# 4_Shutdown.net
KiCad netlist of a schematic drawn in Altium Designer
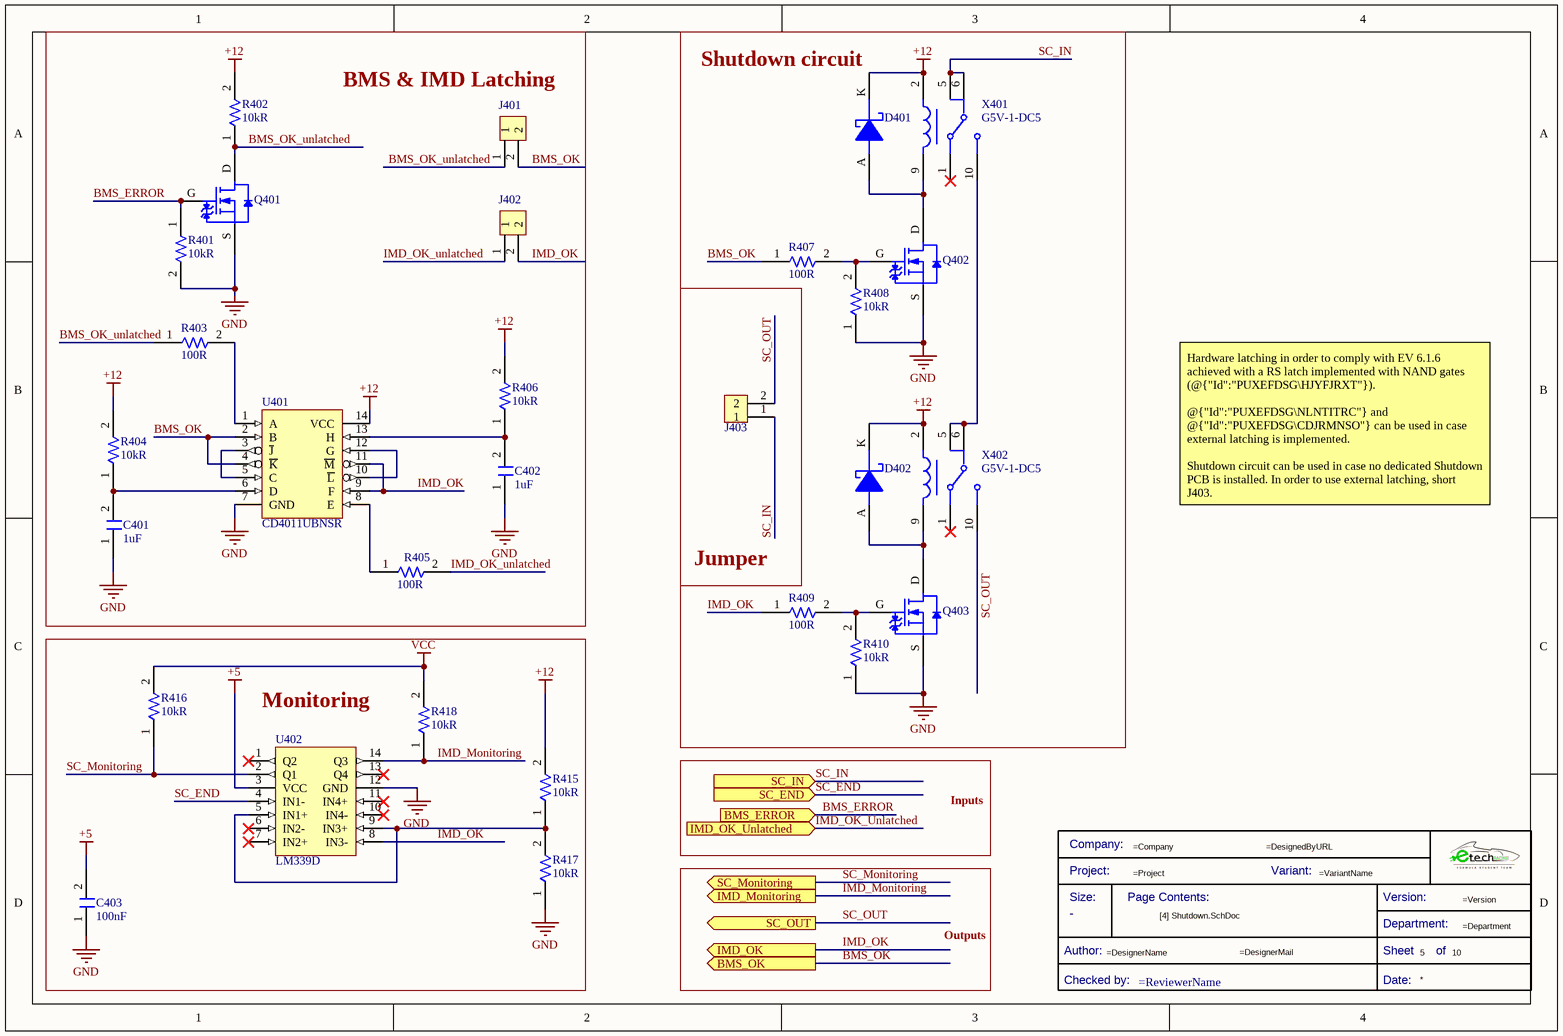
[diagram p0: [4] Shutdown.SchDoc]

(export (version "E")
  (design (tool "Eeschema 10.0.6"))
  (components
    (comp (ref "*")
      (value "Title Block_template")
      (description "Standard Title Block")
      (fields (field (name "SIZE") "-"))
      (libsource (lib "e-Tech_Racing") (part "Title Block_template"))
    )
    (comp (ref "C401")
      (value "885012207103")
      (footprint "C0805FNPC-R")
      (fields
        (field (name "TOLERANCE") "10%")
        (field (name "CAPACITANCE") "1uF")
        (field (name ".CREATOR") "GP")
      )
      (libsource (lib "Passives") (part "C1u-50V-0805FNPC-X7R"))
    )
    (comp (ref "C402")
      (value "885012207103")
      (footprint "C0805FNPC-R")
      (fields
        (field (name "TOLERANCE") "10%")
        (field (name "CAPACITANCE") "1uF")
        (field (name ".CREATOR") "GP")
      )
      (libsource (lib "Passives") (part "C1u-50V-0805FNPC-X7R"))
    )
    (comp (ref "C403")
      (value "885012207098")
      (footprint "C0805FNPC-R")
      (description "Cap, 0.1ΜF, 50V, 10%, X7R, 0805")
      (fields
        (field (name "TOLERANCE") "10%")
        (field (name "CAPACITANCE") "100nF")
        (field (name ".CREATOR") "DR")
      )
      (libsource (lib "Passives") (part "C100n-50V-0805FNPC-X7R"))
    )
    (comp (ref "D401")
      (value "MBR0530")
      (footprint "DSC-SOD123")
      (description "VR=30V IF=500mA 30pF P=410mW")
      (fields (field (name ".CREATOR") "GP"))
      (libsource (lib "Filter components") (part "DSC-0.5/30-SOD123"))
    )
    (comp (ref "D402")
      (value "MBR0530")
      (footprint "DSC-SOD123")
      (description "VR=30V IF=500mA 30pF P=410mW")
      (fields (field (name ".CREATOR") "GP"))
      (libsource (lib "Filter components") (part "DSC-0.5/30-SOD123"))
    )
    (comp (ref "J401")
      (value "61300211121")
      (footprint "J_Pinheader_1x2")
      (description "CONN HEADER 2 POS 2.54")
      (fields (field (name "MANUFACTURER") "Molex") (field (name ".CREATOR") "GP"))
      (libsource (lib "Electromechanical") (part "J_Jumper"))
    )
    (comp (ref "J402")
      (value "61300211121")
      (footprint "J_Pinheader_1x2")
      (description "CONN HEADER 2 POS 2.54")
      (fields (field (name "MANUFACTURER") "Molex") (field (name ".CREATOR") "GP"))
      (libsource (lib "Electromechanical") (part "J_Jumper"))
    )
    (comp (ref "J403")
      (value "61300211121")
      (footprint "J_Pinheader_1x2")
      (description "CONN HEADER 2 POS 2.54")
      (fields (field (name "MANUFACTURER") "Molex") (field (name ".CREATOR") "GP"))
      (libsource (lib "") (part "J_Jumper_1"))
    )
    (comp (ref "Q401")
      (value "CPH3455-TL-H")
      (footprint "TRT-NCH-3/35-CPH")
      (description "CPH3455-TL-H N-channel MOSFET Transistor; 3 A; 35 V; 3-Pin CPH")
      (fields (field (name "MANUFACTURER") "ON Semiconductor") (field (name ".CREATOR") "GP"))
      (libsource (lib "Semiconductor") (part "TRT-NCH-3/35-CPH"))
    )
    (comp (ref "Q402")
      (value "CPH3455-TL-H")
      (footprint "TRT-NCH-3/35-CPH")
      (description "CPH3455-TL-H N-channel MOSFET Transistor; 3 A; 35 V; 3-Pin CPH")
      (fields (field (name "MANUFACTURER") "ON Semiconductor") (field (name ".CREATOR") "GP"))
      (libsource (lib "Semiconductor") (part "TRT-NCH-3/35-CPH"))
    )
    (comp (ref "Q403")
      (value "CPH3455-TL-H")
      (footprint "TRT-NCH-3/35-CPH")
      (description "CPH3455-TL-H N-channel MOSFET Transistor; 3 A; 35 V; 3-Pin CPH")
      (fields (field (name "MANUFACTURER") "ON Semiconductor") (field (name ".CREATOR") "GP"))
      (libsource (lib "Semiconductor") (part "TRT-NCH-3/35-CPH"))
    )
    (comp (ref "R401")
      (value "CR0805-JW-103ELF")
      (footprint "R0805FTK")
      (fields
        (field (name "TOLERANCE") "5%")
        (field (name "RESISTANCE") "10kR")
        (field (name ".CREATOR") "DR")
      )
      (libsource (lib "Passives") (part "R10k-0805FTK"))
    )
    (comp (ref "R402")
      (value "CR0805-JW-103ELF")
      (footprint "R0805FTK")
      (fields
        (field (name "TOLERANCE") "5%")
        (field (name "RESISTANCE") "10kR")
        (field (name ".CREATOR") "DR")
      )
      (libsource (lib "Passives") (part "R10k-0805FTK"))
    )
    (comp (ref "R403")
      (value "CR0805-FX-1000ELF")
      (footprint "R0805FTK")
      (description "Res Thick Film 0805 100 Ohm 1% 1/8W ±100ppm/°C Molded SMD SMD Paper Tape on Plastic Reel")
      (fields
        (field (name "TOLERANCE") "1%")
        (field (name "RESISTANCE") "100R")
        (field (name ".CREATOR") "DR")
      )
      (libsource (lib "Passives") (part "R100-0805FTK"))
    )
    (comp (ref "R404")
      (value "CR0805-JW-103ELF")
      (footprint "R0805FTK")
      (fields
        (field (name "TOLERANCE") "5%")
        (field (name "RESISTANCE") "10kR")
        (field (name ".CREATOR") "DR")
      )
      (libsource (lib "Passives") (part "R10k-0805FTK"))
    )
    (comp (ref "R405")
      (value "CR0805-FX-1000ELF")
      (footprint "R0805FTK")
      (description "Res Thick Film 0805 100 Ohm 1% 1/8W ±100ppm/°C Molded SMD SMD Paper Tape on Plastic Reel")
      (fields
        (field (name "TOLERANCE") "1%")
        (field (name "RESISTANCE") "100R")
        (field (name ".CREATOR") "DR")
      )
      (libsource (lib "Passives") (part "R100-0805FTK"))
    )
    (comp (ref "R406")
      (value "CR0805-JW-103ELF")
      (footprint "R0805FTK")
      (fields
        (field (name "TOLERANCE") "5%")
        (field (name "RESISTANCE") "10kR")
        (field (name ".CREATOR") "DR")
      )
      (libsource (lib "Passives") (part "R10k-0805FTK"))
    )
    (comp (ref "R407")
      (value "CR0805-FX-1000ELF")
      (footprint "R0805FTK")
      (description "Res Thick Film 0805 100 Ohm 1% 1/8W ±100ppm/°C Molded SMD SMD Paper Tape on Plastic Reel")
      (fields
        (field (name "TOLERANCE") "1%")
        (field (name "RESISTANCE") "100R")
        (field (name ".CREATOR") "DR")
      )
      (libsource (lib "Passives") (part "R100-0805FTK"))
    )
    (comp (ref "R408")
      (value "CR0805-JW-103ELF")
      (footprint "R0805FTK")
      (fields
        (field (name "TOLERANCE") "5%")
        (field (name "RESISTANCE") "10kR")
        (field (name ".CREATOR") "DR")
      )
      (libsource (lib "Passives") (part "R10k-0805FTK"))
    )
    (comp (ref "R409")
      (value "CR0805-FX-1000ELF")
      (footprint "R0805FTK")
      (description "Res Thick Film 0805 100 Ohm 1% 1/8W ±100ppm/°C Molded SMD SMD Paper Tape on Plastic Reel")
      (fields
        (field (name "TOLERANCE") "1%")
        (field (name "RESISTANCE") "100R")
        (field (name ".CREATOR") "DR")
      )
      (libsource (lib "Passives") (part "R100-0805FTK"))
    )
    (comp (ref "R410")
      (value "CR0805-JW-103ELF")
      (footprint "R0805FTK")
      (fields
        (field (name "TOLERANCE") "5%")
        (field (name "RESISTANCE") "10kR")
        (field (name ".CREATOR") "DR")
      )
      (libsource (lib "Passives") (part "R10k-0805FTK"))
    )
    (comp (ref "R415")
      (value "CR0805-JW-103ELF")
      (footprint "R0805FTK")
      (fields
        (field (name "TOLERANCE") "5%")
        (field (name "RESISTANCE") "10kR")
        (field (name ".CREATOR") "DR")
      )
      (libsource (lib "Passives") (part "R10k-0805FTK"))
    )
    (comp (ref "R416")
      (value "CR0805-JW-103ELF")
      (footprint "R0805FTK")
      (fields
        (field (name "TOLERANCE") "5%")
        (field (name "RESISTANCE") "10kR")
        (field (name ".CREATOR") "DR")
      )
      (libsource (lib "Passives") (part "R10k-0805FTK"))
    )
    (comp (ref "R417")
      (value "CR0805-JW-103ELF")
      (footprint "R0805FTK")
      (fields
        (field (name "TOLERANCE") "5%")
        (field (name "RESISTANCE") "10kR")
        (field (name ".CREATOR") "DR")
      )
      (libsource (lib "Passives") (part "R10k-0805FTK"))
    )
    (comp (ref "R418")
      (value "CR0805-JW-103ELF")
      (footprint "R0805FTK")
      (fields
        (field (name "TOLERANCE") "5%")
        (field (name "RESISTANCE") "10kR")
        (field (name ".CREATOR") "DR")
      )
      (libsource (lib "Passives") (part "R10k-0805FTK"))
    )
    (comp (ref "U401")
      (value "CD4011UBSNR")
      (footprint "ARRAY_4_NAND")
      (description "CD4011UB Cmos Quad 2-INPUT Nand")
      (fields
        (field (name "MANUFACTURER") "Texas Instruments")
        (field (name "MANUFACTURER PART NUMBER") "CD4011UBNSR")
        (field (name ".CREATOR") "DO")
      )
      (libsource (lib "Integrated circuits") (part "Array_4_NAND"))
    )
    (comp (ref "U402")
      (value "LM339D")
      (footprint "Array_4_Amp_LM339D")
      (description "Comparator Quad ±18V/36V 14-Pin SOIC Tube")
      (fields
        (field (name "MANUFACTURER") "Texas Instruments")
        (field (name "MANUFACTURER PART NUMBER") "LM339D")
        (field (name ".CREATOR") "DO")
      )
      (libsource (lib "Integrated circuits") (part "Array_4_Amp_LM339D"))
    )
    (comp (ref "X401")
      (value "G5V-1-DC5")
      (footprint "Relay_G5V-1-DC5")
      (description "Electromechanical Relay SPDT 1A 5VDC 167Ohm Through Hole")
      (fields
        (field (name "MANUFACTURER") "Omron")
        (field (name "SUPPLIER PART NUMBER 1") "G5V-1-DC5")
        (field (name ".CREATOR") "DO")
      )
      (libsource (lib "Electromechanical") (part "Relay_G5V-1-DC5"))
    )
    (comp (ref "X402")
      (value "G5V-1-DC5")
      (footprint "Relay_G5V-1-DC5")
      (description "Electromechanical Relay SPDT 1A 5VDC 167Ohm Through Hole")
      (fields
        (field (name "MANUFACTURER") "Omron")
        (field (name "SUPPLIER PART NUMBER 1") "G5V-1-DC5")
        (field (name ".CREATOR") "DO")
      )
      (libsource (lib "Electromechanical") (part "Relay_G5V-1-DC5"))
    )
  )
  (nets
    (net (code "1") (name "+5") (class "Default")
      (node (ref "C403") (pin "2") (pinfunction "2_2") (pintype "passive"))
      (node (ref "U402") (pin "3") (pinfunction "VCC_3") (pintype "power_in"))
    )
    (net (code "2") (name "+12") (class "Default")
      (node (ref "D401") (pin "K") (pinfunction "K_K") (pintype "passive"))
      (node (ref "D402") (pin "K") (pinfunction "K_K") (pintype "passive"))
      (node (ref "R402") (pin "2") (pinfunction "2_2") (pintype "passive"))
      (node (ref "R404") (pin "2") (pinfunction "2_2") (pintype "passive"))
      (node (ref "R406") (pin "2") (pinfunction "2_2") (pintype "passive"))
      (node (ref "R415") (pin "2") (pinfunction "2_2") (pintype "passive"))
      (node (ref "U401") (pin "14") (pinfunction "VCC_14") (pintype "power_in"))
      (node (ref "X401") (pin "2") (pinfunction "2_2") (pintype "passive"))
      (node (ref "X402") (pin "2") (pinfunction "2_2") (pintype "passive"))
    )
    (net (code "3") (name "/BMS_ERROR") (class "Default")
      (node (ref "Q401") (pin "G") (pinfunction "G_G") (pintype "passive"))
      (node (ref "R401") (pin "1") (pinfunction "1_1") (pintype "passive"))
    )
    (net (code "4") (name "/BMS_OK") (class "Default")
      (node (ref "J401") (pin "2") (pinfunction "2_2") (pintype "passive"))
      (node (ref "R407") (pin "1") (pinfunction "1_1") (pintype "passive"))
      (node (ref "U401") (pin "2") (pinfunction "B_2") (pintype "input"))
      (node (ref "U401") (pin "4") (pinfunction "~{K}_4") (pintype "output"))
    )
    (net (code "5") (name "/BMS_OK_unlatched") (class "Default")
      (node (ref "J401") (pin "1") (pinfunction "1_1") (pintype "passive"))
      (node (ref "Q401") (pin "D") (pinfunction "D_D") (pintype "passive"))
      (node (ref "R402") (pin "1") (pinfunction "1_1") (pintype "passive"))
      (node (ref "R403") (pin "1") (pinfunction "1_1") (pintype "passive"))
    )
    (net (code "6") (name "/IMD_Monitoring") (class "Default")
      (node (ref "R418") (pin "1") (pinfunction "1_1") (pintype "passive"))
      (node (ref "U402") (pin "14") (pinfunction "Q3_14") (pintype "output"))
    )
    (net (code "7") (name "/IMD_OK") (class "Default")
      (node (ref "J402") (pin "2") (pinfunction "2_2") (pintype "passive"))
      (node (ref "R409") (pin "1") (pinfunction "1_1") (pintype "passive"))
      (node (ref "U401") (pin "11") (pinfunction "~{M}_11") (pintype "output"))
      (node (ref "U401") (pin "9") (pinfunction "F_9") (pintype "input"))
      (node (ref "U402") (pin "8") (pinfunction "IN3-_8") (pintype "input"))
    )
    (net (code "9") (name "/IMD_OK_unlatched") (class "Default")
      (node (ref "J402") (pin "1") (pinfunction "1_1") (pintype "passive"))
      (node (ref "R405") (pin "2") (pinfunction "2_2") (pintype "passive"))
    )
    (net (code "10") (name "/SC_END") (class "Default")
      (node (ref "U402") (pin "4") (pinfunction "IN1-_4") (pintype "input"))
    )
    (net (code "11") (name "/SC_IN") (class "Default")
      (node (ref "J403") (pin "1") (pinfunction "1_1") (pintype "passive"))
      (node (ref "X401") (pin "5") (pinfunction "5_5") (pintype "passive"))
      (node (ref "X401") (pin "6") (pinfunction "6_6") (pintype "passive"))
    )
    (net (code "12") (name "/SC_Monitoring") (class "Default")
      (node (ref "R416") (pin "1") (pinfunction "1_1") (pintype "passive"))
      (node (ref "U402") (pin "2") (pinfunction "Q1_2") (pintype "output"))
    )
    (net (code "13") (name "/SC_OUT") (class "Default")
      (node (ref "J403") (pin "2") (pinfunction "2_2") (pintype "passive"))
      (node (ref "X402") (pin "10") (pinfunction "10_10") (pintype "passive"))
    )
    (net (code "14") (name "GND") (class "Default")
      (node (ref "C401") (pin "1") (pinfunction "1_1") (pintype "passive"))
      (node (ref "C402") (pin "1") (pinfunction "1_1") (pintype "passive"))
      (node (ref "C403") (pin "1") (pinfunction "1_1") (pintype "passive"))
      (node (ref "Q401") (pin "S") (pinfunction "S_S") (pintype "passive"))
      (node (ref "Q402") (pin "S") (pinfunction "S_S") (pintype "passive"))
      (node (ref "Q403") (pin "S") (pinfunction "S_S") (pintype "passive"))
      (node (ref "R401") (pin "2") (pinfunction "2_2") (pintype "passive"))
      (node (ref "R408") (pin "1") (pinfunction "1_1") (pintype "passive"))
      (node (ref "R410") (pin "1") (pinfunction "1_1") (pintype "passive"))
      (node (ref "R417") (pin "1") (pinfunction "1_1") (pintype "passive"))
      (node (ref "U401") (pin "7") (pinfunction "GND_7") (pintype "power_in"))
      (node (ref "U402") (pin "12") (pinfunction "GND_12") (pintype "power_in"))
    )
    (net (code "15") (name "Net-(D401-PadA)") (class "Default")
      (node (ref "D401") (pin "A") (pinfunction "A_A") (pintype "passive"))
      (node (ref "Q402") (pin "D") (pinfunction "D_D") (pintype "passive"))
      (node (ref "X401") (pin "9") (pinfunction "9_9") (pintype "passive"))
    )
    (net (code "16") (name "Net-(D402-PadA)") (class "Default")
      (node (ref "D402") (pin "A") (pinfunction "A_A") (pintype "passive"))
      (node (ref "Q403") (pin "D") (pinfunction "D_D") (pintype "passive"))
      (node (ref "X402") (pin "9") (pinfunction "9_9") (pintype "passive"))
    )
    (net (code "17") (name "Net-(Q402-PadG)") (class "Default")
      (node (ref "Q402") (pin "G") (pinfunction "G_G") (pintype "passive"))
      (node (ref "R407") (pin "2") (pinfunction "2_2") (pintype "passive"))
      (node (ref "R408") (pin "2") (pinfunction "2_2") (pintype "passive"))
    )
    (net (code "18") (name "Net-(Q403-PadG)") (class "Default")
      (node (ref "Q403") (pin "G") (pinfunction "G_G") (pintype "passive"))
      (node (ref "R409") (pin "2") (pinfunction "2_2") (pintype "passive"))
      (node (ref "R410") (pin "2") (pinfunction "2_2") (pintype "passive"))
    )
    (net (code "19") (name "Net-(U401-A)") (class "Default")
      (node (ref "R403") (pin "2") (pinfunction "2_2") (pintype "passive"))
      (node (ref "U401") (pin "1") (pinfunction "A_1") (pintype "input"))
    )
    (net (code "20") (name "Net-(U401-C)") (class "Default")
      (node (ref "U401") (pin "3") (pinfunction "~{J}_3") (pintype "output"))
      (node (ref "U401") (pin "5") (pinfunction "C_5") (pintype "input"))
    )
    (net (code "21") (name "Net-(U401-D)") (class "Default")
      (node (ref "C401") (pin "2") (pinfunction "2_2") (pintype "passive"))
      (node (ref "R404") (pin "1") (pinfunction "1_1") (pintype "passive"))
      (node (ref "U401") (pin "6") (pinfunction "D_6") (pintype "input"))
    )
    (net (code "22") (name "Net-(U401-E)") (class "Default")
      (node (ref "R405") (pin "1") (pinfunction "1_1") (pintype "passive"))
      (node (ref "U401") (pin "8") (pinfunction "E_8") (pintype "input"))
    )
    (net (code "23") (name "Net-(U401-G)") (class "Default")
      (node (ref "U401") (pin "10") (pinfunction "~{L}_10") (pintype "output"))
      (node (ref "U401") (pin "12") (pinfunction "G_12") (pintype "input"))
    )
    (net (code "24") (name "Net-(U401-H)") (class "Default")
      (node (ref "C402") (pin "2") (pinfunction "2_2") (pintype "passive"))
      (node (ref "R406") (pin "1") (pinfunction "1_1") (pintype "passive"))
      (node (ref "U401") (pin "13") (pinfunction "H_13") (pintype "input"))
    )
    (net (code "25") (name "Net-(U402-IN1+)") (class "Default")
      (node (ref "R415") (pin "1") (pinfunction "1_1") (pintype "passive"))
      (node (ref "R417") (pin "2") (pinfunction "2_2") (pintype "passive"))
      (node (ref "U402") (pin "5") (pinfunction "IN1+_5") (pintype "input"))
      (node (ref "U402") (pin "9") (pinfunction "IN3+_9") (pintype "input"))
    )
    (net (code "26") (name "Net-(X401-Pad10)") (class "Default")
      (node (ref "X401") (pin "10") (pinfunction "10_10") (pintype "passive"))
      (node (ref "X402") (pin "5") (pinfunction "5_5") (pintype "passive"))
      (node (ref "X402") (pin "6") (pinfunction "6_6") (pintype "passive"))
    )
    (net (code "27") (name "VCC") (class "Default")
      (node (ref "R416") (pin "2") (pinfunction "2_2") (pintype "passive"))
      (node (ref "R418") (pin "2") (pinfunction "2_2") (pintype "passive"))
    )
    (net (code "28") (name "unconnected-(U402-IN2+-Pad7)") (class "Default")
      (node (ref "U402") (pin "7") (pinfunction "IN2+_7") (pintype "input+no_connect"))
    )
    (net (code "29") (name "unconnected-(U402-IN2--Pad6)") (class "Default")
      (node (ref "U402") (pin "6") (pinfunction "IN2-_6") (pintype "input+no_connect"))
    )
    (net (code "30") (name "unconnected-(U402-IN4+-Pad11)") (class "Default")
      (node (ref "U402") (pin "11") (pinfunction "IN4+_11") (pintype "input+no_connect"))
    )
    (net (code "31") (name "unconnected-(U402-IN4--Pad10)") (class "Default")
      (node (ref "U402") (pin "10") (pinfunction "IN4-_10") (pintype "input+no_connect"))
    )
    (net (code "32") (name "unconnected-(U402-Q2-Pad1)") (class "Default")
      (node (ref "U402") (pin "1") (pinfunction "Q2_1") (pintype "output+no_connect"))
    )
    (net (code "33") (name "unconnected-(U402-Q4-Pad13)") (class "Default")
      (node (ref "U402") (pin "13") (pinfunction "Q4_13") (pintype "output+no_connect"))
    )
    (net (code "34") (name "unconnected-(X401-Pad1)") (class "Default")
      (node (ref "X401") (pin "1") (pinfunction "1_1") (pintype "passive+no_connect"))
    )
    (net (code "35") (name "unconnected-(X402-Pad1)") (class "Default")
      (node (ref "X402") (pin "1") (pinfunction "1_1") (pintype "passive+no_connect"))
    )
  )
)
